# Sheet1.net
KiCad netlist of a schematic drawn in Altium Designer
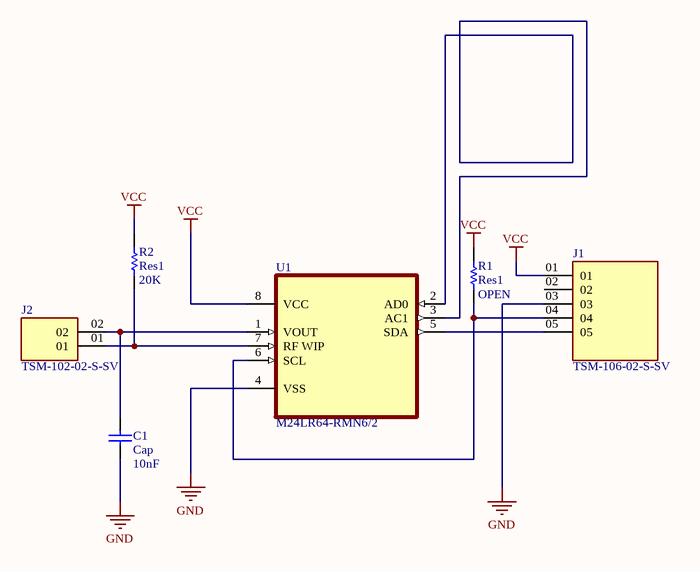
[diagram p0: Sheet1.SchDoc]

(export (version "E")
  (design (tool "Eeschema 10.0.6"))
  (components
    (comp (ref "C1")
      (value "Cap")
      (footprint "0402")
      (description "Capacitor")
      (fields (field (name "ALTIUM_VALUE") "10nF") (field (name "PUBLISHER") "Altium Limited"))
      (libsource (lib "Miscellaneous Devices") (part "Cap"))
    )
    (comp (ref "J1")
      (value "TSM-106-02-S-SV")
      (footprint "SAMTEC_TSM-106-02-T-SH")
      (fields (field (name "MF") "Samtec") (field (name "MP") "TSM-106-02-T-SH"))
      (libsource (lib "TSM-106-02-T-SH") (part "TSM-106-02-T-SH"))
    )
    (comp (ref "J2")
      (value "TSM-102-02-S-SV")
      (footprint "SAMTEC_TSM-102-02-S-SV")
      (description "Conn Unshrouded Header HDR 2 POS 2.54mm Solder ST SMD T/R")
      (fields (field (name "MF") "Samtec Inc.") (field (name "MP") "TSM-102-02-S-SV-P-TR"))
      (libsource (lib "TSM-102-02-S-SV") (part "TSM-102-02-S-SV"))
    )
    (comp (ref "R1")
      (value "Res1")
      (footprint "AXIAL-0.3")
      (description "Resistor")
      (fields (field (name "ALTIUM_VALUE") "OPEN") (field (name "PUBLISHER") "Altium Limited"))
      (libsource (lib "Miscellaneous Devices") (part "Res1"))
    )
    (comp (ref "R2")
      (value "Res1")
      (footprint "AXIAL-0.3")
      (description "Resistor")
      (fields (field (name "ALTIUM_VALUE") "20K") (field (name "PUBLISHER") "Altium Limited"))
      (libsource (lib "Miscellaneous Devices") (part "Res1"))
    )
    (comp (ref "U1")
      (value "M24LR64-RMN6/2")
      (footprint "SOIC127P600X175-8N")
      (description "64 Kbit EEPROM")
      (fields (field (name "MP") "M24LR64-RMN6-2"))
      (libsource (lib "M24LR64-RMN6_2") (part "M24LR64-RMN6/2"))
    )
  )
  (nets
    (net (code "1") (name "GND") (class "Default")
      (node (ref "C1") (pin "1") (pinfunction "1_1") (pintype "passive"))
      (node (ref "J1") (pin "03") (pinfunction "03_03") (pintype "passive"))
      (node (ref "U1") (pin "4") (pinfunction "VSS_4") (pintype "power_in"))
    )
    (net (code "2") (name "Net-(U1-AC1)") (class "Default")
      (node (ref "U1") (pin "2") (pinfunction "AD0_2") (pintype "input"))
      (node (ref "U1") (pin "3") (pinfunction "AC1_3") (pintype "output"))
    )
    (net (code "3") (name "Net-(U1-RF_WIP)") (class "Default")
      (node (ref "J2") (pin "01") (pinfunction "01_01") (pintype "passive"))
      (node (ref "R2") (pin "1") (pinfunction "1_1") (pintype "passive"))
      (node (ref "U1") (pin "7") (pinfunction "RF_WIP_7") (pintype "input"))
    )
    (net (code "4") (name "Net-(U1-SCL)") (class "Default")
      (node (ref "J1") (pin "04") (pinfunction "04_04") (pintype "passive"))
      (node (ref "R1") (pin "1") (pinfunction "1_1") (pintype "passive"))
      (node (ref "U1") (pin "6") (pinfunction "SCL_6") (pintype "input"))
    )
    (net (code "5") (name "Net-(U1-SDA)") (class "Default")
      (node (ref "J1") (pin "05") (pinfunction "05_05") (pintype "passive"))
      (node (ref "U1") (pin "5") (pinfunction "SDA_5") (pintype "output"))
    )
    (net (code "6") (name "Net-(U1-VOUT)") (class "Default")
      (node (ref "C1") (pin "2") (pinfunction "2_2") (pintype "passive"))
      (node (ref "J2") (pin "02") (pinfunction "02_02") (pintype "passive"))
      (node (ref "U1") (pin "1") (pinfunction "VOUT_1") (pintype "input"))
    )
    (net (code "7") (name "VCC") (class "Default")
      (node (ref "J1") (pin "01") (pinfunction "01_01") (pintype "passive"))
      (node (ref "R1") (pin "2") (pinfunction "2_2") (pintype "passive"))
      (node (ref "R2") (pin "2") (pinfunction "2_2") (pintype "passive"))
      (node (ref "U1") (pin "8") (pinfunction "VCC_8") (pintype "power_in"))
    )
    (net (code "8") (name "unconnected-(J1-Pad02)") (class "Default")
      (node (ref "J1") (pin "02") (pinfunction "02_02") (pintype "passive"))
    )
  )
)
